# Power_Supply.net
KiCad netlist of a schematic drawn in Altium Designer
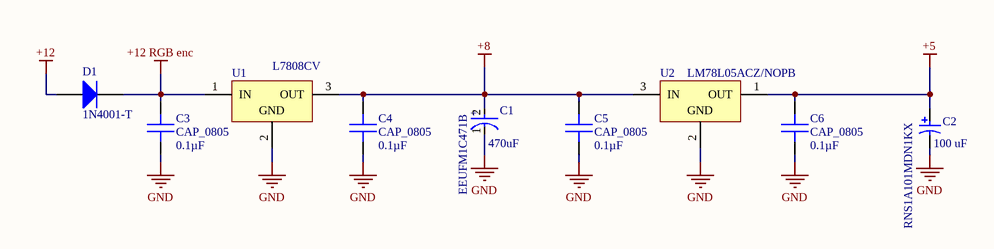
[diagram p0: Power Supply.SchDoc]

(export (version "E")
  (design (tool "Eeschema 10.0.6"))
  (components
    (comp (ref "C1")
      (value "EEUFM1C471B")
      (footprint "FP-RAD-TH-D_10_0_5-L_12_5-MFG")
      (description "Aluminum Electrolytic Capacitors (Radial Lead Type) 470uF ±20% 16V")
      (fields (field (name "TOLERANCE") "20%") (field (name "CAPACITANCE") "470uF"))
      (libsource (lib "Altium Content Vault") (part "203bc49f2ac43e59fd269a8c329ed05"))
    )
    (comp (ref "C2")
      (value "RNS1A101MDN1KX")
      (footprint "NIC-RNS-8x11.5-2_V")
      (description "Aluminum Electrolytic Capacitor, 100 uF +/-20%, 10 V, -55 to 105 degC, 2-Pin THD, RoHS")
      (fields (field (name "MANUFACTURER") "Nichicon") (field (name "RATED CAPACITANCE") "100 uF"))
      (libsource (lib "Altium Content Vault") (part "NIC-CAP-P-2"))
    )
    (comp (ref "C3")
      (value "CAP_0805")
      (footprint "0805_CAPACITOR_DCACERES")
      (description "Capacitor SMD, encapsulado 0805")
      (fields (field (name "ALTIUM_VALUE") "0.1µF"))
      (libsource (lib "PF_Schlib") (part "CAPACITOR_0805_Caceres"))
    )
    (comp (ref "C4")
      (value "CAP_0805")
      (footprint "0805_CAPACITOR_DCACERES")
      (description "Capacitor SMD, encapsulado 0805")
      (fields (field (name "ALTIUM_VALUE") "0.1µF"))
      (libsource (lib "PF_Schlib") (part "CAPACITOR_0805_Caceres"))
    )
    (comp (ref "C5")
      (value "CAP_0805")
      (footprint "0805_CAPACITOR_DCACERES")
      (description "Capacitor SMD, encapsulado 0805")
      (fields (field (name "ALTIUM_VALUE") "0.1µF"))
      (libsource (lib "PF_Schlib") (part "CAPACITOR_0805_Caceres"))
    )
    (comp (ref "C6")
      (value "CAP_0805")
      (footprint "0805_CAPACITOR_DCACERES")
      (description "Capacitor SMD, encapsulado 0805")
      (fields (field (name "ALTIUM_VALUE") "0.1µF"))
      (libsource (lib "PF_Schlib") (part "CAPACITOR_0805_Caceres"))
    )
    (comp (ref "D1")
      (value "1N4001-T")
      (footprint "DIOD-DO-41-P-2_V")
      (description "1.0 A Rectifier, 15 pF, 50 V, -65 to 150 degC, 2-Pin DO-41 Plastic, RoHS, Tape and Reel")
      (fields (field (name "MANUFACTURER") "Diodes Inc"))
      (libsource (lib "Altium Content Vault") (part "DIOD-D-A1K2-2"))
    )
    (comp (ref "U1")
      (value "L7808CV")
      (footprint "TO220")
      (description "Positive Voltage Regulator, 8V, 3-Pin TO-220")
      (libsource (lib "Altium Content Vault") (part "PM-REG-L4940-SIL3"))
    )
    (comp (ref "U2")
      (value "LM78L05ACZ/NOPB")
      (footprint "LP0003A")
      (description "3-Terminal Positive Regulator, 5 Vout, 3-pin TO-92, Pb-Free")
      (fields (field (name "MANUFACTURER") "Texas Instruments"))
      (libsource (lib "Altium Content Vault") (part "PM-REG-LM78L05-SIL3"))
    )
  )
  (nets
    (net (code "1") (name "+5") (class "Default")
      (node (ref "C2") (pin "1") (pinfunction "1_1") (pintype "passive"))
      (node (ref "C6") (pin "1") (pinfunction "1_1") (pintype "passive"))
      (node (ref "U2") (pin "1") (pinfunction "OUT_1") (pintype "power_in"))
    )
    (net (code "2") (name "+8") (class "Default")
      (node (ref "C1") (pin "2") (pinfunction "A_2") (pintype "passive"))
      (node (ref "C4") (pin "1") (pinfunction "1_1") (pintype "passive"))
      (node (ref "C5") (pin "1") (pinfunction "1_1") (pintype "passive"))
      (node (ref "U1") (pin "3") (pinfunction "OUT_3") (pintype "power_in"))
      (node (ref "U2") (pin "3") (pinfunction "IN_3") (pintype "power_in"))
    )
    (net (code "3") (name "+12") (class "Default")
      (node (ref "D1") (pin "1") (pinfunction "A_1") (pintype "passive"))
    )
    (net (code "4") (name "+12 RGB enc") (class "Default")
      (node (ref "C3") (pin "1") (pinfunction "1_1") (pintype "passive"))
      (node (ref "D1") (pin "2") (pinfunction "K_2") (pintype "passive"))
      (node (ref "U1") (pin "1") (pinfunction "IN_1") (pintype "power_in"))
    )
    (net (code "5") (name "GND") (class "Default")
      (node (ref "C1") (pin "1") (pinfunction "C_1") (pintype "passive"))
      (node (ref "C2") (pin "2") (pinfunction "2_2") (pintype "passive"))
      (node (ref "C3") (pin "2") (pinfunction "2_2") (pintype "passive"))
      (node (ref "C4") (pin "2") (pinfunction "2_2") (pintype "passive"))
      (node (ref "C5") (pin "2") (pinfunction "2_2") (pintype "passive"))
      (node (ref "C6") (pin "2") (pinfunction "2_2") (pintype "passive"))
      (node (ref "U1") (pin "2") (pinfunction "GND_2") (pintype "power_in"))
      (node (ref "U2") (pin "2") (pinfunction "GND_2") (pintype "power_in"))
    )
  )
)
